# Non-contact_Diameter_Sensor.net
KiCad netlist of a schematic drawn in EAGLE
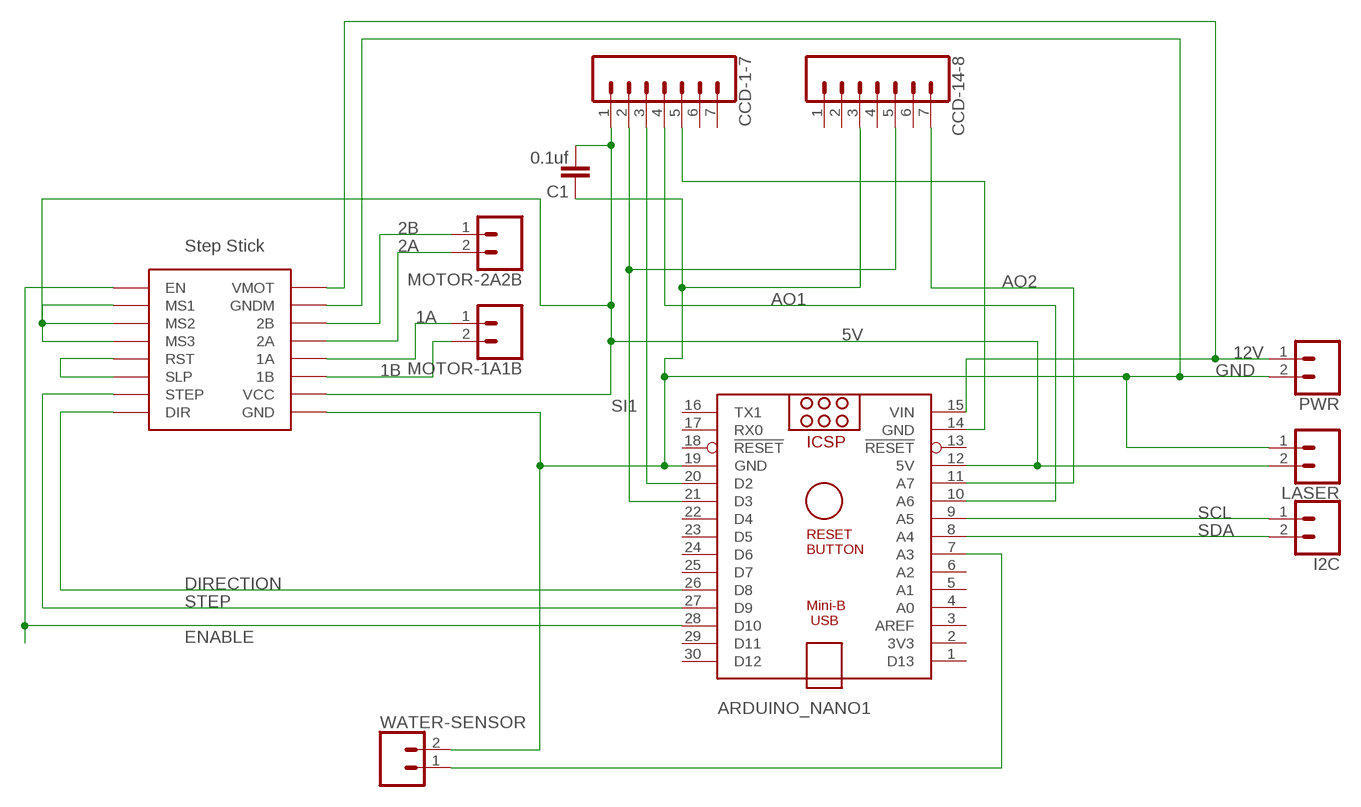
[diagram p0: schematic, sheet 1]

(export (version "E")
  (design (tool "Eeschema 10.0.6"))
  (components
    (comp (ref "ARDUINO_NANO1")
      (value "ARDUINO_NANO")
      (footprint "eagle-import:ARDUINO_NANO")
      (libsource (lib "eagle-import") (part "ARDUINO_NANO"))
    )
    (comp (ref "C1")
      (value "0.1uf")
      (footprint "eagle-import:C050-025X075")
      (libsource (lib "eagle-import") (part "C-EU050-025X075"))
    )
    (comp (ref "CCD-1-7")
      (value "CONN_07")
      (footprint "eagle-import:1X07")
      (libsource (lib "eagle-import") (part "CONN_07"))
    )
    (comp (ref "CCD-14-8")
      (value "CONN_07")
      (footprint "eagle-import:1X07")
      (libsource (lib "eagle-import") (part "CONN_07"))
    )
    (comp (ref "I2C")
      (value "CONN_023.5MM")
      (footprint "eagle-import:SCREWTERMINAL-3.5MM-2")
      (libsource (lib "eagle-import") (part "CONN_023.5MM"))
    )
    (comp (ref "LASER")
      (value "CONN_023.5MM")
      (footprint "eagle-import:SCREWTERMINAL-3.5MM-2")
      (libsource (lib "eagle-import") (part "CONN_023.5MM"))
    )
    (comp (ref "MOTOR-1A1B")
      (value "CONN_023.5MM")
      (footprint "eagle-import:SCREWTERMINAL-3.5MM-2")
      (libsource (lib "eagle-import") (part "CONN_023.5MM"))
    )
    (comp (ref "MOTOR-2A2B")
      (value "CONN_023.5MM")
      (footprint "eagle-import:SCREWTERMINAL-3.5MM-2")
      (libsource (lib "eagle-import") (part "CONN_023.5MM"))
    )
    (comp (ref "PWR")
      (value "CONN_023.5MM")
      (footprint "eagle-import:SCREWTERMINAL-3.5MM-2")
      (libsource (lib "eagle-import") (part "CONN_023.5MM"))
    )
    (comp (ref "U$1")
      (value "STEP-STICK")
      (footprint "eagle-import:STEP-STICK")
      (libsource (lib "eagle-import") (part "STEP-STICK"))
    )
    (comp (ref "WATER-SENSOR")
      (value "CONN_02")
      (footprint "eagle-import:1X02")
      (libsource (lib "eagle-import") (part "CONN_02"))
    )
  )
  (nets
    (net (code "1") (name "/1A") (class "Default")
      (node (ref "MOTOR-1A1B") (pin "1") (pinfunction "1_1") (pintype "passive"))
      (node (ref "U$1") (pin "1A") (pinfunction "1A_1A") (pintype "bidirectional"))
    )
    (net (code "2") (name "/1B") (class "Default")
      (node (ref "MOTOR-1A1B") (pin "2") (pinfunction "2_2") (pintype "passive"))
      (node (ref "U$1") (pin "1B") (pinfunction "1B_1B") (pintype "bidirectional"))
    )
    (net (code "3") (name "/2A") (class "Default")
      (node (ref "MOTOR-2A2B") (pin "2") (pinfunction "2_2") (pintype "passive"))
      (node (ref "U$1") (pin "2A") (pinfunction "2A_2A") (pintype "bidirectional"))
    )
    (net (code "4") (name "/2B") (class "Default")
      (node (ref "MOTOR-2A2B") (pin "1") (pinfunction "1_1") (pintype "passive"))
      (node (ref "U$1") (pin "2B") (pinfunction "2B_2B") (pintype "bidirectional"))
    )
    (net (code "5") (name "/5V") (class "Default")
      (node (ref "ARDUINO_NANO1") (pin "12") (pinfunction "5V_12") (pintype "power_in"))
      (node (ref "C1") (pin "2") (pinfunction "2_2") (pintype "passive"))
      (node (ref "CCD-1-7") (pin "1") (pinfunction "1_1") (pintype "passive"))
      (node (ref "LASER") (pin "2") (pinfunction "2_2") (pintype "passive"))
      (node (ref "U$1") (pin "MS1") (pinfunction "MS1_MS1") (pintype "bidirectional"))
      (node (ref "U$1") (pin "MS2") (pinfunction "MS2_MS2") (pintype "bidirectional"))
      (node (ref "U$1") (pin "MS3") (pinfunction "MS3_MS3") (pintype "bidirectional"))
      (node (ref "U$1") (pin "VCC") (pinfunction "VCC_VCC") (pintype "bidirectional"))
    )
    (net (code "6") (name "/12V") (class "Default")
      (node (ref "ARDUINO_NANO1") (pin "15") (pinfunction "VIN_15") (pintype "power_in"))
      (node (ref "PWR") (pin "1") (pinfunction "1_1") (pintype "passive"))
      (node (ref "U$1") (pin "VMOT") (pinfunction "VMOT_VMOT") (pintype "bidirectional"))
    )
    (net (code "7") (name "/AO1") (class "Default")
      (node (ref "ARDUINO_NANO1") (pin "10") (pinfunction "A6_10") (pintype "bidirectional"))
      (node (ref "CCD-1-7") (pin "4") (pinfunction "4_4") (pintype "passive"))
    )
    (net (code "8") (name "/AO2") (class "Default")
      (node (ref "ARDUINO_NANO1") (pin "11") (pinfunction "A7_11") (pintype "bidirectional"))
      (node (ref "CCD-14-8") (pin "7") (pinfunction "7_7") (pintype "passive"))
    )
    (net (code "9") (name "/DIRECTION") (class "Default")
      (node (ref "ARDUINO_NANO1") (pin "26") (pinfunction "D8_26") (pintype "bidirectional"))
      (node (ref "U$1") (pin "DIR") (pinfunction "DIR_DIR") (pintype "bidirectional"))
    )
    (net (code "10") (name "/ENABLE") (class "Default")
      (node (ref "ARDUINO_NANO1") (pin "28") (pinfunction "D10_28") (pintype "bidirectional"))
      (node (ref "U$1") (pin "EN") (pinfunction "EN_EN") (pintype "bidirectional"))
    )
    (net (code "11") (name "/GND") (class "Default")
      (node (ref "ARDUINO_NANO1") (pin "14") (pinfunction "GND_14") (pintype "power_in"))
      (node (ref "ARDUINO_NANO1") (pin "19") (pinfunction "GND_19") (pintype "power_in"))
      (node (ref "C1") (pin "1") (pinfunction "1_1") (pintype "passive"))
      (node (ref "CCD-1-7") (pin "5") (pinfunction "5_5") (pintype "passive"))
      (node (ref "CCD-14-8") (pin "3") (pinfunction "3_3") (pintype "passive"))
      (node (ref "LASER") (pin "1") (pinfunction "1_1") (pintype "passive"))
      (node (ref "PWR") (pin "2") (pinfunction "2_2") (pintype "passive"))
      (node (ref "U$1") (pin "GND") (pinfunction "GND_GND") (pintype "bidirectional"))
      (node (ref "U$1") (pin "GNDM") (pinfunction "GNDM_GNDM") (pintype "bidirectional"))
      (node (ref "WATER-SENSOR") (pin "2") (pinfunction "2_2") (pintype "passive"))
    )
    (net (code "12") (name "/SCL") (class "Default")
      (node (ref "ARDUINO_NANO1") (pin "9") (pinfunction "A5_9") (pintype "bidirectional"))
      (node (ref "I2C") (pin "1") (pinfunction "1_1") (pintype "passive"))
    )
    (net (code "13") (name "/SDA") (class "Default")
      (node (ref "ARDUINO_NANO1") (pin "8") (pinfunction "A4_8") (pintype "bidirectional"))
      (node (ref "I2C") (pin "2") (pinfunction "2_2") (pintype "passive"))
    )
    (net (code "14") (name "/SI1") (class "Default")
      (node (ref "ARDUINO_NANO1") (pin "21") (pinfunction "D3_21") (pintype "bidirectional"))
      (node (ref "CCD-1-7") (pin "2") (pinfunction "2_2") (pintype "passive"))
      (node (ref "CCD-14-8") (pin "5") (pinfunction "5_5") (pintype "passive"))
    )
    (net (code "15") (name "/STEP") (class "Default")
      (node (ref "ARDUINO_NANO1") (pin "27") (pinfunction "D9_27") (pintype "bidirectional"))
      (node (ref "U$1") (pin "SPT") (pinfunction "STEP_SPT") (pintype "bidirectional"))
    )
    (net (code "16") (name "Net-(ARDUINO_NANO1-A3)") (class "Default")
      (node (ref "ARDUINO_NANO1") (pin "7") (pinfunction "A3_7") (pintype "bidirectional"))
      (node (ref "WATER-SENSOR") (pin "1") (pinfunction "1_1") (pintype "passive"))
    )
    (net (code "17") (name "Net-(ARDUINO_NANO1-D2)") (class "Default")
      (node (ref "ARDUINO_NANO1") (pin "20") (pinfunction "D2_20") (pintype "bidirectional"))
      (node (ref "CCD-1-7") (pin "3") (pinfunction "3_3") (pintype "passive"))
    )
    (net (code "18") (name "Net-(U$1-PadRST)") (class "Default")
      (node (ref "U$1") (pin "RST") (pinfunction "RST_RST") (pintype "bidirectional"))
      (node (ref "U$1") (pin "SLP") (pinfunction "SLP_SLP") (pintype "bidirectional"))
    )
    (net (code "19") (name "unconnected-(ARDUINO_NANO1-3V3-Pad2)") (class "Default")
      (node (ref "ARDUINO_NANO1") (pin "2") (pinfunction "3V3_2") (pintype "output"))
    )
    (net (code "20") (name "unconnected-(ARDUINO_NANO1-A0-Pad4)") (class "Default")
      (node (ref "ARDUINO_NANO1") (pin "4") (pinfunction "A0_4") (pintype "bidirectional"))
    )
    (net (code "21") (name "unconnected-(ARDUINO_NANO1-A1-Pad5)") (class "Default")
      (node (ref "ARDUINO_NANO1") (pin "5") (pinfunction "A1_5") (pintype "bidirectional"))
    )
    (net (code "22") (name "unconnected-(ARDUINO_NANO1-A2-Pad6)") (class "Default")
      (node (ref "ARDUINO_NANO1") (pin "6") (pinfunction "A2_6") (pintype "bidirectional"))
    )
    (net (code "23") (name "unconnected-(ARDUINO_NANO1-AREF-Pad3)") (class "Default")
      (node (ref "ARDUINO_NANO1") (pin "3") (pinfunction "AREF_3") (pintype "input"))
    )
    (net (code "24") (name "unconnected-(ARDUINO_NANO1-D4-Pad22)") (class "Default")
      (node (ref "ARDUINO_NANO1") (pin "22") (pinfunction "D4_22") (pintype "bidirectional"))
    )
    (net (code "25") (name "unconnected-(ARDUINO_NANO1-D5-Pad23)") (class "Default")
      (node (ref "ARDUINO_NANO1") (pin "23") (pinfunction "D5_23") (pintype "bidirectional"))
    )
    (net (code "26") (name "unconnected-(ARDUINO_NANO1-D6-Pad24)") (class "Default")
      (node (ref "ARDUINO_NANO1") (pin "24") (pinfunction "D6_24") (pintype "bidirectional"))
    )
    (net (code "27") (name "unconnected-(ARDUINO_NANO1-D7-Pad25)") (class "Default")
      (node (ref "ARDUINO_NANO1") (pin "25") (pinfunction "D7_25") (pintype "bidirectional"))
    )
    (net (code "28") (name "unconnected-(ARDUINO_NANO1-D11-Pad29)") (class "Default")
      (node (ref "ARDUINO_NANO1") (pin "29") (pinfunction "D11_29") (pintype "bidirectional"))
    )
    (net (code "29") (name "unconnected-(ARDUINO_NANO1-D12-Pad30)") (class "Default")
      (node (ref "ARDUINO_NANO1") (pin "30") (pinfunction "D12_30") (pintype "bidirectional"))
    )
    (net (code "30") (name "unconnected-(ARDUINO_NANO1-D13-Pad1)") (class "Default")
      (node (ref "ARDUINO_NANO1") (pin "1") (pinfunction "D13_1") (pintype "bidirectional"))
    )
    (net (code "31") (name "unconnected-(ARDUINO_NANO1-RX0-Pad17)") (class "Default")
      (node (ref "ARDUINO_NANO1") (pin "17") (pinfunction "RX0_17") (pintype "bidirectional"))
    )
    (net (code "32") (name "unconnected-(ARDUINO_NANO1-TX1-Pad16)") (class "Default")
      (node (ref "ARDUINO_NANO1") (pin "16") (pinfunction "TX1_16") (pintype "bidirectional"))
    )
    (net (code "33") (name "unconnected-(ARDUINO_NANO1-~{RESET}-Pad13)") (class "Default")
      (node (ref "ARDUINO_NANO1") (pin "13") (pinfunction "~{RESET}_13") (pintype "input"))
    )
    (net (code "34") (name "unconnected-(ARDUINO_NANO1-~{RESET}-Pad18)") (class "Default")
      (node (ref "ARDUINO_NANO1") (pin "18") (pinfunction "~{RESET}_18") (pintype "input"))
    )
    (net (code "35") (name "unconnected-(CCD-1-7-Pad6)") (class "Default")
      (node (ref "CCD-1-7") (pin "6") (pinfunction "6_6") (pintype "passive"))
    )
    (net (code "36") (name "unconnected-(CCD-1-7-Pad7)") (class "Default")
      (node (ref "CCD-1-7") (pin "7") (pinfunction "7_7") (pintype "passive"))
    )
    (net (code "37") (name "unconnected-(CCD-14-8-Pad1)") (class "Default")
      (node (ref "CCD-14-8") (pin "1") (pinfunction "1_1") (pintype "passive"))
    )
    (net (code "38") (name "unconnected-(CCD-14-8-Pad2)") (class "Default")
      (node (ref "CCD-14-8") (pin "2") (pinfunction "2_2") (pintype "passive"))
    )
    (net (code "39") (name "unconnected-(CCD-14-8-Pad4)") (class "Default")
      (node (ref "CCD-14-8") (pin "4") (pinfunction "4_4") (pintype "passive"))
    )
    (net (code "40") (name "unconnected-(CCD-14-8-Pad6)") (class "Default")
      (node (ref "CCD-14-8") (pin "6") (pinfunction "6_6") (pintype "passive"))
    )
  )
)
